# carrier_sengi.net
KiCad netlist of a schematic drawn in EAGLE
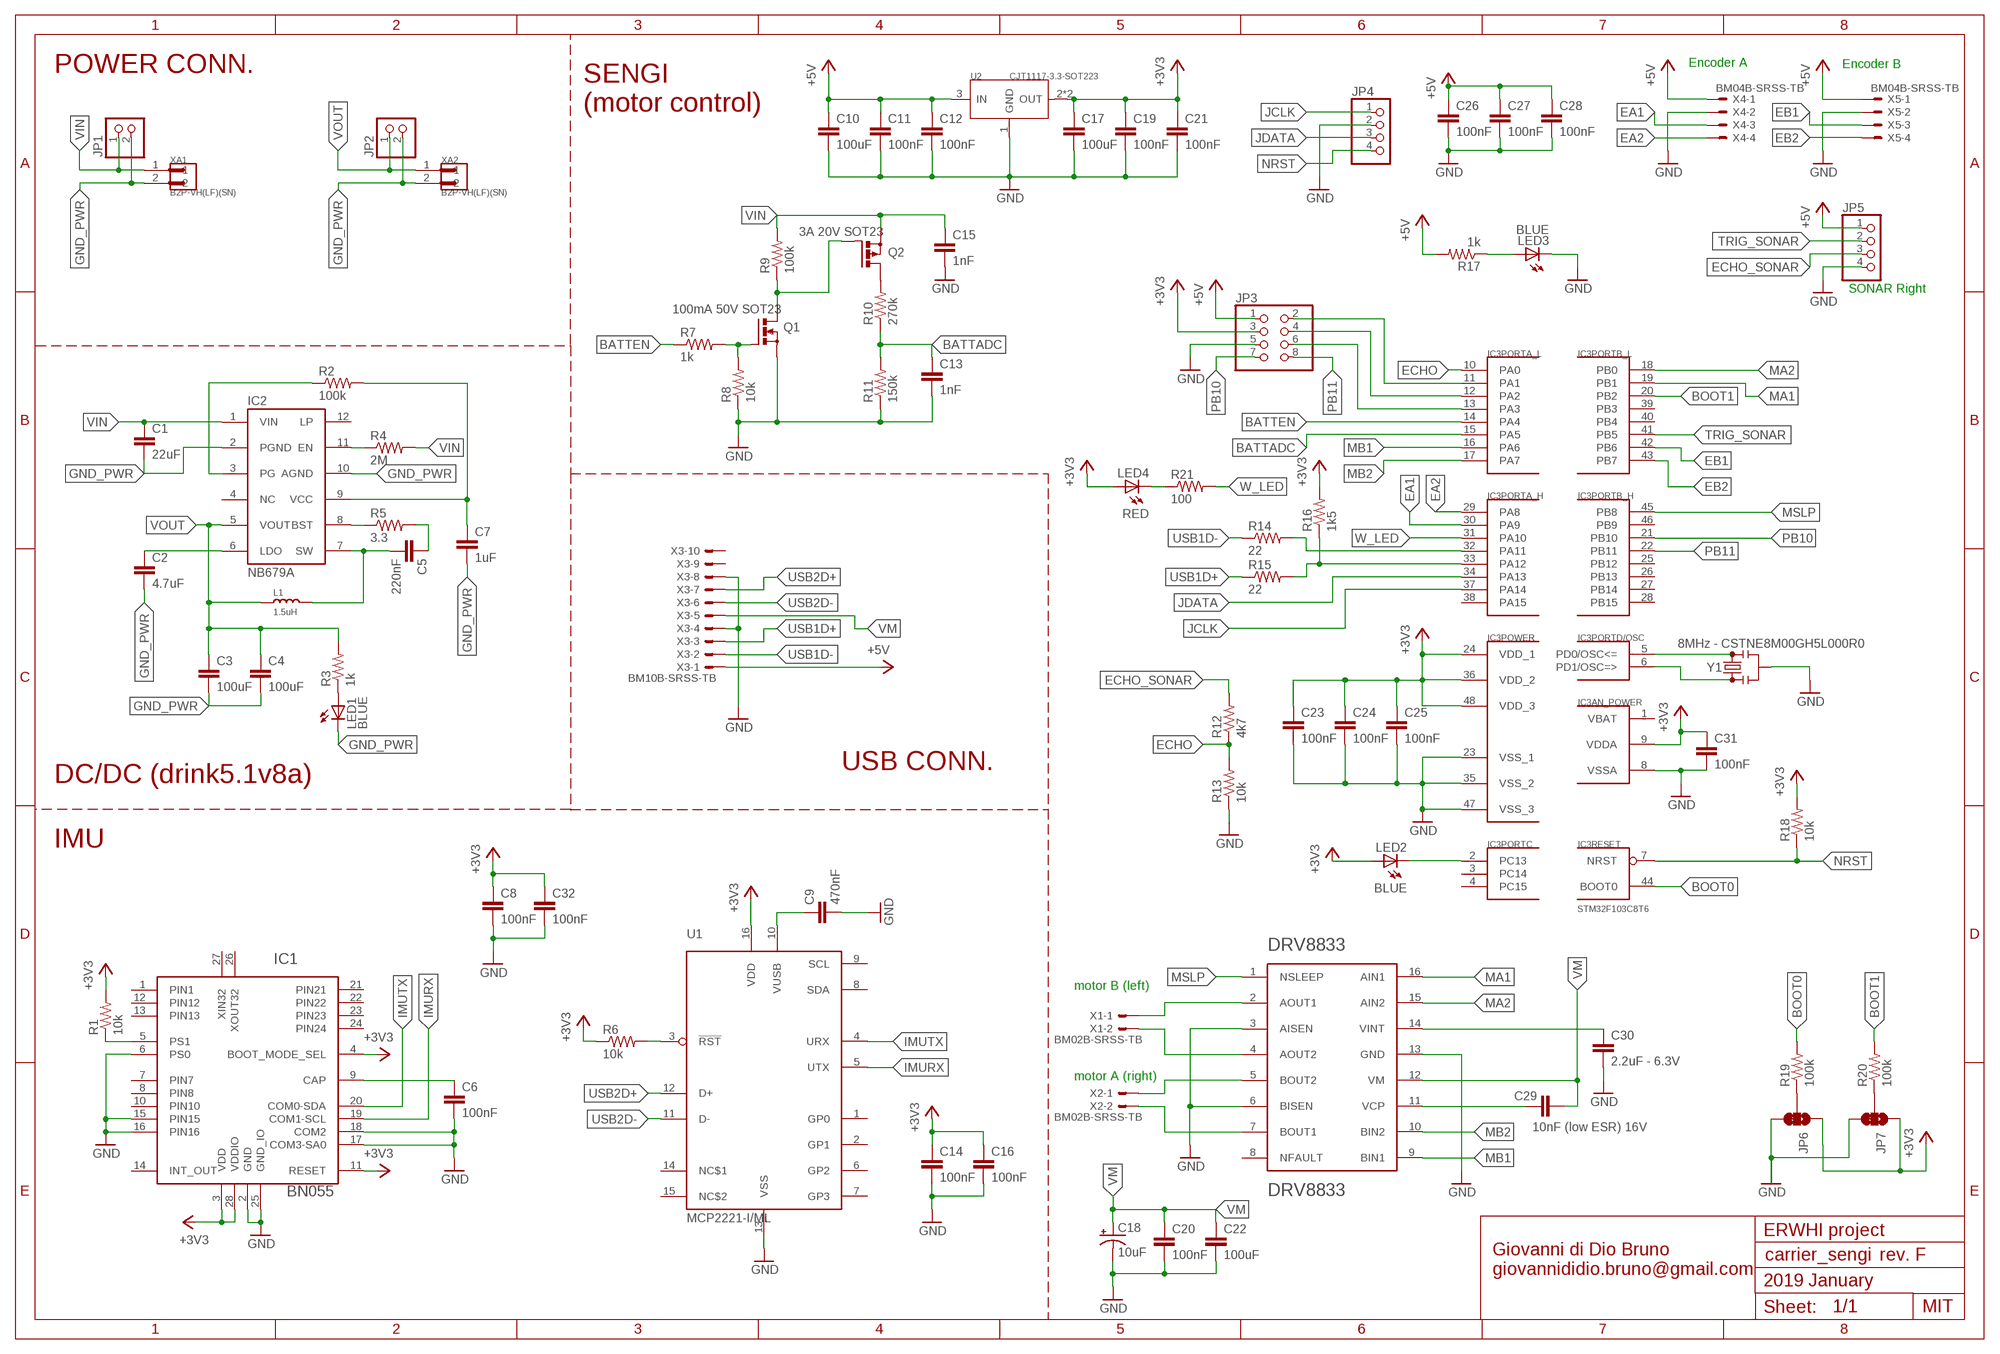
[diagram p0: schematic, sheet 1]

(export (version "E")
  (design (tool "Eeschema 10.0.6"))
  (components
    (comp (ref "C1")
      (value "22uF")
      (footprint "eagle-import:C0805")
      (libsource (lib "eagle-import") (part "C-EUC0805"))
    )
    (comp (ref "C2")
      (value "4.7uF")
      (footprint "eagle-import:C0603")
      (libsource (lib "eagle-import") (part "C-EUC0603"))
    )
    (comp (ref "C3")
      (value "100uF")
      (footprint "eagle-import:C0805")
      (libsource (lib "eagle-import") (part "C-EUC0805"))
    )
    (comp (ref "C4")
      (value "100uF")
      (footprint "eagle-import:C0805")
      (libsource (lib "eagle-import") (part "C-EUC0805"))
    )
    (comp (ref "C5")
      (value "220nF")
      (footprint "eagle-import:C0603")
      (libsource (lib "eagle-import") (part "C-EUC0603"))
    )
    (comp (ref "C6")
      (value "100nF")
      (footprint "eagle-import:C0402")
      (libsource (lib "eagle-import") (part "C-EUC0402"))
    )
    (comp (ref "C7")
      (value "1uF")
      (footprint "eagle-import:C0603")
      (libsource (lib "eagle-import") (part "C-EUC0603"))
    )
    (comp (ref "C8")
      (value "100nF")
      (footprint "eagle-import:C0402")
      (libsource (lib "eagle-import") (part "C-EUC0402"))
    )
    (comp (ref "C9")
      (value "470nF")
      (footprint "eagle-import:C0402")
      (libsource (lib "eagle-import") (part "C-EUC0402"))
    )
    (comp (ref "C10")
      (value "100uF")
      (footprint "eagle-import:C0603")
      (libsource (lib "eagle-import") (part "C-EUC0603"))
    )
    (comp (ref "C11")
      (value "100nF")
      (footprint "eagle-import:C0402")
      (libsource (lib "eagle-import") (part "C-EUC0402"))
    )
    (comp (ref "C12")
      (value "100nF")
      (footprint "eagle-import:C0402")
      (libsource (lib "eagle-import") (part "C-EUC0402"))
    )
    (comp (ref "C13")
      (value "1nF")
      (footprint "eagle-import:C0402")
      (libsource (lib "eagle-import") (part "C-EUC0402"))
    )
    (comp (ref "C14")
      (value "100nF")
      (footprint "eagle-import:C0402")
      (libsource (lib "eagle-import") (part "C-EUC0402"))
    )
    (comp (ref "C15")
      (value "1nF")
      (footprint "eagle-import:C0402")
      (libsource (lib "eagle-import") (part "C-EUC0402"))
    )
    (comp (ref "C16")
      (value "100nF")
      (footprint "eagle-import:C0402")
      (libsource (lib "eagle-import") (part "C-EUC0402"))
    )
    (comp (ref "C17")
      (value "100uF")
      (footprint "eagle-import:C0603")
      (libsource (lib "eagle-import") (part "C-EUC0603"))
    )
    (comp (ref "C18")
      (value "10uF")
      (footprint "eagle-import:EIA3216")
      (libsource (lib "eagle-import") (part "10UF-POLAR-EIA3216-16V-10%(TANT)"))
    )
    (comp (ref "C19")
      (value "100nF")
      (footprint "eagle-import:C0402")
      (libsource (lib "eagle-import") (part "C-EUC0402"))
    )
    (comp (ref "C20")
      (value "100nF")
      (footprint "eagle-import:C0402")
      (libsource (lib "eagle-import") (part "C-EUC0402"))
    )
    (comp (ref "C21")
      (value "100nF")
      (footprint "eagle-import:C0402")
      (libsource (lib "eagle-import") (part "C-EUC0402"))
    )
    (comp (ref "C22")
      (value "100uF")
      (footprint "eagle-import:C0603")
      (libsource (lib "eagle-import") (part "C-EUC0603"))
    )
    (comp (ref "C23")
      (value "100nF")
      (footprint "eagle-import:C0402")
      (libsource (lib "eagle-import") (part "C-EUC0402"))
    )
    (comp (ref "C24")
      (value "100nF")
      (footprint "eagle-import:C0402")
      (libsource (lib "eagle-import") (part "C-EUC0402"))
    )
    (comp (ref "C25")
      (value "100nF")
      (footprint "eagle-import:C0402")
      (libsource (lib "eagle-import") (part "C-EUC0402"))
    )
    (comp (ref "C26")
      (value "100nF")
      (footprint "eagle-import:C0402")
      (libsource (lib "eagle-import") (part "C-EUC0402"))
    )
    (comp (ref "C27")
      (value "100nF")
      (footprint "eagle-import:C0402")
      (libsource (lib "eagle-import") (part "C-EUC0402"))
    )
    (comp (ref "C28")
      (value "100nF")
      (footprint "eagle-import:C0402")
      (libsource (lib "eagle-import") (part "C-EUC0402"))
    )
    (comp (ref "C29")
      (value "10nF (low ESR) 16V")
      (footprint "eagle-import:C0402")
      (libsource (lib "eagle-import") (part "C-EUC0402"))
    )
    (comp (ref "C30")
      (value "2.2uF - 6.3V")
      (footprint "eagle-import:C0402")
      (libsource (lib "eagle-import") (part "C-EUC0402"))
    )
    (comp (ref "C31")
      (value "100nF")
      (footprint "eagle-import:C0402")
      (libsource (lib "eagle-import") (part "C-EUC0402"))
    )
    (comp (ref "C32")
      (value "100nF")
      (footprint "eagle-import:C0402")
      (libsource (lib "eagle-import") (part "C-EUC0402"))
    )
    (comp (ref "IC1")
      (value "BN055")
      (footprint "eagle-import:LGA-28_3.80X5.20_0.5")
      (fields (field (name "PART_NUMBER") "BNO055"))
      (libsource (lib "eagle-import") (part "1658_BNO055"))
    )
    (comp (ref "IC2")
      (value "NB679A")
      (footprint "eagle-import:QFN12_2X3")
      (libsource (lib "eagle-import") (part "NB679A"))
    )
    (comp (ref "IC3")
      (value "STM32F103C8T6")
      (footprint "eagle-import:TQFP48")
      (libsource (lib "eagle-import") (part "STM32F10XCXT6"))
    )
    (comp (ref "IC4")
      (value "DRV8833PWP")
      (footprint "eagle-import:SOP65P640X120-17N")
      (libsource (lib "eagle-import") (part "DRV8833"))
    )
    (comp (ref "JP1")
      (value "PINHD-1X2")
      (footprint "eagle-import:1X02")
      (libsource (lib "eagle-import") (part "PINHD-1X2"))
    )
    (comp (ref "JP2")
      (value "PINHD-1X2")
      (footprint "eagle-import:1X02")
      (libsource (lib "eagle-import") (part "PINHD-1X2"))
    )
    (comp (ref "JP3")
      (value "PINHD-2X4")
      (footprint "eagle-import:2X04")
      (libsource (lib "eagle-import") (part "PINHD-2X4"))
    )
    (comp (ref "JP4")
      (value "PINHD-1X4")
      (footprint "eagle-import:1X04")
      (libsource (lib "eagle-import") (part "PINHD-1X4"))
    )
    (comp (ref "JP5")
      (value "PINHD-1X4")
      (footprint "eagle-import:1X04")
      (libsource (lib "eagle-import") (part "PINHD-1X4"))
    )
    (comp (ref "JP6")
      (value "JUMPER-SMT_3_1-NC_TRACE_NO-SILK")
      (footprint "eagle-import:SMT-JUMPER_3_1-NC_TRACE_NO-SILK")
      (libsource (lib "eagle-import") (part "JUMPER-SMT_3_1-NC_TRACE_NO-SILK"))
    )
    (comp (ref "JP7")
      (value "JUMPER-SMT_3_1-NC_TRACE_NO-SILK")
      (footprint "eagle-import:SMT-JUMPER_3_1-NC_TRACE_NO-SILK")
      (libsource (lib "eagle-import") (part "JUMPER-SMT_3_1-NC_TRACE_NO-SILK"))
    )
    (comp (ref "L1")
      (value "1.5uH")
      (footprint "eagle-import:SMD-2P-L6.0XW6.0XH3.0MM")
      (fields (field (name "MPN") "CSAB0630-100M"))
      (libsource (lib "eagle-import") (part "SMD-INDUCTOR-10UH-20%(2P-6X6MM)'0630'"))
    )
    (comp (ref "LED1")
      (value "BLUE")
      (footprint "eagle-import:CHIP-LED0603")
      (libsource (lib "eagle-import") (part "LEDCHIP-LED0603"))
    )
    (comp (ref "LED2")
      (value "BLUE")
      (footprint "eagle-import:CHIP-LED0603")
      (libsource (lib "eagle-import") (part "LEDCHIP-LED0603"))
    )
    (comp (ref "LED3")
      (value "BLUE")
      (footprint "eagle-import:CHIP-LED0603")
      (libsource (lib "eagle-import") (part "LEDCHIP-LED0603"))
    )
    (comp (ref "LED4")
      (value "RED")
      (footprint "eagle-import:CHIP-LED0603")
      (libsource (lib "eagle-import") (part "LEDCHIP-LED0603"))
    )
    (comp (ref "Q1")
      (value "100mA 50V SOT23")
      (footprint "eagle-import:SOT-23")
      (libsource (lib "eagle-import") (part "IRLML6344"))
    )
    (comp (ref "Q2")
      (value "3A 20V SOT23")
      (footprint "eagle-import:SOT-23")
      (libsource (lib "eagle-import") (part "IRLML6402"))
    )
    (comp (ref "R1")
      (value "10k")
      (footprint "eagle-import:R0402")
      (libsource (lib "eagle-import") (part "R-US_R0402"))
    )
    (comp (ref "R2")
      (value "100k")
      (footprint "eagle-import:R0402")
      (libsource (lib "eagle-import") (part "R-US_R0402"))
    )
    (comp (ref "R3")
      (value "1k")
      (footprint "eagle-import:R0402")
      (libsource (lib "eagle-import") (part "R-US_R0402"))
    )
    (comp (ref "R4")
      (value "2M")
      (footprint "eagle-import:R0603")
      (libsource (lib "eagle-import") (part "R-US_R0603"))
    )
    (comp (ref "R5")
      (value "3.3")
      (footprint "eagle-import:R0603")
      (libsource (lib "eagle-import") (part "R-US_R0603"))
    )
    (comp (ref "R6")
      (value "10k")
      (footprint "eagle-import:R0402")
      (libsource (lib "eagle-import") (part "R-US_R0402"))
    )
    (comp (ref "R7")
      (value "1k")
      (footprint "eagle-import:R0402")
      (libsource (lib "eagle-import") (part "R-US_R0402"))
    )
    (comp (ref "R8")
      (value "10k")
      (footprint "eagle-import:R0402")
      (libsource (lib "eagle-import") (part "R-US_R0402"))
    )
    (comp (ref "R9")
      (value "100k")
      (footprint "eagle-import:R0402")
      (libsource (lib "eagle-import") (part "R-US_R0402"))
    )
    (comp (ref "R10")
      (value "270k")
      (footprint "eagle-import:R0402")
      (libsource (lib "eagle-import") (part "R-US_R0402"))
    )
    (comp (ref "R11")
      (value "150k")
      (footprint "eagle-import:R0402")
      (libsource (lib "eagle-import") (part "R-US_R0402"))
    )
    (comp (ref "R12")
      (value "4k7")
      (footprint "eagle-import:R0402")
      (libsource (lib "eagle-import") (part "R-US_R0402"))
    )
    (comp (ref "R13")
      (value "10k")
      (footprint "eagle-import:R0402")
      (libsource (lib "eagle-import") (part "R-US_R0402"))
    )
    (comp (ref "R14")
      (value "22")
      (footprint "eagle-import:R0402")
      (libsource (lib "eagle-import") (part "R-US_R0402"))
    )
    (comp (ref "R15")
      (value "22")
      (footprint "eagle-import:R0402")
      (libsource (lib "eagle-import") (part "R-US_R0402"))
    )
    (comp (ref "R16")
      (value "1k5")
      (footprint "eagle-import:R0402")
      (libsource (lib "eagle-import") (part "R-US_R0402"))
    )
    (comp (ref "R17")
      (value "1k")
      (footprint "eagle-import:R0402")
      (libsource (lib "eagle-import") (part "R-US_R0402"))
    )
    (comp (ref "R18")
      (value "10k")
      (footprint "eagle-import:R0402")
      (libsource (lib "eagle-import") (part "R-US_R0402"))
    )
    (comp (ref "R19")
      (value "100k")
      (footprint "eagle-import:R0402")
      (libsource (lib "eagle-import") (part "R-US_R0402"))
    )
    (comp (ref "R20")
      (value "100k")
      (footprint "eagle-import:R0402")
      (libsource (lib "eagle-import") (part "R-US_R0402"))
    )
    (comp (ref "R21")
      (value "100")
      (footprint "eagle-import:R0402")
      (libsource (lib "eagle-import") (part "R-US_R0402"))
    )
    (comp (ref "U1")
      (value "MCP2221-I/ML")
      (footprint "eagle-import:QFN16-4X4")
      (libsource (lib "eagle-import") (part "MCP2221-I/ML"))
    )
    (comp (ref "U2")
      (value "CJT1117-3.3-SOT223")
      (footprint "eagle-import:SOT-223")
      (fields (field (name "MPN") "CJT1117-3.3"))
      (libsource (lib "eagle-import") (part "PMIC-CJT1117-3.3(SOT223)"))
    )
    (comp (ref "X1")
      (value "BM02B-SRSS-TB")
      (footprint "eagle-import:BM02B-SRSS-TB")
      (libsource (lib "eagle-import") (part "?M02B-SRSS-TBB"))
    )
    (comp (ref "X2")
      (value "BM02B-SRSS-TB")
      (footprint "eagle-import:BM02B-SRSS-TB")
      (libsource (lib "eagle-import") (part "?M02B-SRSS-TBB"))
    )
    (comp (ref "X3")
      (value "BM10B-SRSS-TB")
      (footprint "eagle-import:BM10B-SRSS-TB")
      (libsource (lib "eagle-import") (part "?M10B-SRSS-TBB"))
    )
    (comp (ref "X4")
      (value "BM04B-SRSS-TB")
      (footprint "eagle-import:BM04B-SRSS-TB")
      (libsource (lib "eagle-import") (part "?M04B-SRSS-TBB"))
    )
    (comp (ref "X5")
      (value "BM04B-SRSS-TB")
      (footprint "eagle-import:BM04B-SRSS-TB")
      (libsource (lib "eagle-import") (part "?M04B-SRSS-TBB"))
    )
    (comp (ref "XA1")
      (value "B2P-VH(LF)(SN)")
      (footprint "eagle-import:JST_B2P-VH(LF)(SN)")
      (fields (field (name "MF") "JST") (field (name "MP") "B2P-VH_LF__SN_"))
      (libsource (lib "eagle-import") (part "B2P-VH(LF)(SN)"))
    )
    (comp (ref "XA2")
      (value "B2P-VH(LF)(SN)")
      (footprint "eagle-import:JST_B2P-VH(LF)(SN)")
      (fields (field (name "MF") "JST") (field (name "MP") "B2P-VH_LF__SN_"))
      (libsource (lib "eagle-import") (part "B2P-VH(LF)(SN)"))
    )
    (comp (ref "Y1")
      (value "8MHz - CSTNE8M00GH5L000R0")
      (footprint "eagle-import:RESONATOR-SMD-3.2X1.3")
      (libsource (lib "eagle-import") (part "RESONATOR-8MHZSMD_3.2X1.3"))
    )
  )
  (nets
    (net (code "1") (name "+3V3") (class "Default")
      (node (ref "C14") (pin "1") (pinfunction "1_1") (pintype "passive"))
      (node (ref "C16") (pin "1") (pinfunction "1_1") (pintype "passive"))
      (node (ref "C17") (pin "1") (pinfunction "1_1") (pintype "passive"))
      (node (ref "C19") (pin "1") (pinfunction "1_1") (pintype "passive"))
      (node (ref "C21") (pin "1") (pinfunction "1_1") (pintype "passive"))
      (node (ref "C23") (pin "1") (pinfunction "1_1") (pintype "passive"))
      (node (ref "C24") (pin "1") (pinfunction "1_1") (pintype "passive"))
      (node (ref "C25") (pin "1") (pinfunction "1_1") (pintype "passive"))
      (node (ref "C31") (pin "1") (pinfunction "1_1") (pintype "passive"))
      (node (ref "C32") (pin "1") (pinfunction "1_1") (pintype "passive"))
      (node (ref "C8") (pin "1") (pinfunction "1_1") (pintype "passive"))
      (node (ref "IC1") (pin "11") (pinfunction "RESET_11") (pintype "input"))
      (node (ref "IC1") (pin "28") (pinfunction "VDDIO_28") (pintype "power_in"))
      (node (ref "IC1") (pin "3") (pinfunction "VDD_3") (pintype "power_in"))
      (node (ref "IC1") (pin "4") (pinfunction "BOOT_MODE_SEL_4") (pintype "input"))
      (node (ref "IC3") (pin "24") (pinfunction "VDD_1_24") (pintype "power_in"))
      (node (ref "IC3") (pin "36") (pinfunction "VDD_2_36") (pintype "power_in"))
      (node (ref "IC3") (pin "48") (pinfunction "VDD_3_48") (pintype "power_in"))
      (node (ref "IC3") (pin "9") (pinfunction "VDDA_9") (pintype "power_in"))
      (node (ref "JP3") (pin "3") (pinfunction "3_3") (pintype "passive"))
      (node (ref "JP6") (pin "1") (pinfunction "1_1") (pintype "passive"))
      (node (ref "JP7") (pin "1") (pinfunction "1_1") (pintype "passive"))
      (node (ref "LED2") (pin "A") (pinfunction "A_A") (pintype "passive"))
      (node (ref "LED4") (pin "A") (pinfunction "A_A") (pintype "passive"))
      (node (ref "R1") (pin "2") (pinfunction "2_2") (pintype "passive"))
      (node (ref "R16") (pin "2") (pinfunction "2_2") (pintype "passive"))
      (node (ref "R18") (pin "2") (pinfunction "2_2") (pintype "passive"))
      (node (ref "R6") (pin "1") (pinfunction "1_1") (pintype "passive"))
      (node (ref "U1") (pin "16") (pinfunction "VDD_16") (pintype "power_in"))
      (node (ref "U2") (pin "2") (pinfunction "OUT_2") (pintype "bidirectional"))
      (node (ref "U2") (pin "TER") (pinfunction "OUT_TER") (pintype "bidirectional"))
    )
    (net (code "2") (name "+5V") (class "Default")
      (node (ref "C10") (pin "1") (pinfunction "1_1") (pintype "passive"))
      (node (ref "C11") (pin "1") (pinfunction "1_1") (pintype "passive"))
      (node (ref "C12") (pin "1") (pinfunction "1_1") (pintype "passive"))
      (node (ref "C26") (pin "1") (pinfunction "1_1") (pintype "passive"))
      (node (ref "C27") (pin "1") (pinfunction "1_1") (pintype "passive"))
      (node (ref "C28") (pin "1") (pinfunction "1_1") (pintype "passive"))
      (node (ref "JP3") (pin "1") (pinfunction "1_1") (pintype "passive"))
      (node (ref "JP5") (pin "1") (pinfunction "1_1") (pintype "passive"))
      (node (ref "R17") (pin "2") (pinfunction "2_2") (pintype "passive"))
      (node (ref "U2") (pin "3") (pinfunction "IN_3") (pintype "bidirectional"))
      (node (ref "X3") (pin "1") (pinfunction "S_1") (pintype "passive"))
      (node (ref "X4") (pin "1") (pinfunction "S_1") (pintype "passive"))
      (node (ref "X5") (pin "1") (pinfunction "S_1") (pintype "passive"))
    )
    (net (code "3") (name "/VBAT") (class "Default")
      (node (ref "IC3") (pin "1") (pinfunction "VBAT_1") (pintype "power_in"))
    )
    (net (code "4") (name "BATTADC") (class "Default")
      (node (ref "C13") (pin "1") (pinfunction "1_1") (pintype "passive"))
      (node (ref "IC3") (pin "15") (pinfunction "PA5_15") (pintype "bidirectional"))
      (node (ref "R10") (pin "1") (pinfunction "1_1") (pintype "passive"))
      (node (ref "R11") (pin "2") (pinfunction "2_2") (pintype "passive"))
    )
    (net (code "5") (name "BATTEN") (class "Default")
      (node (ref "IC3") (pin "14") (pinfunction "PA4_14") (pintype "bidirectional"))
      (node (ref "R7") (pin "1") (pinfunction "1_1") (pintype "passive"))
    )
    (net (code "6") (name "BOOT0") (class "Default")
      (node (ref "IC3") (pin "44") (pinfunction "BOOT0_44") (pintype "input"))
      (node (ref "R19") (pin "2") (pinfunction "2_2") (pintype "passive"))
    )
    (net (code "7") (name "BOOT1") (class "Default")
      (node (ref "IC3") (pin "20") (pinfunction "PB2_20") (pintype "bidirectional"))
      (node (ref "R20") (pin "2") (pinfunction "2_2") (pintype "passive"))
    )
    (net (code "8") (name "EA1") (class "Default")
      (node (ref "IC3") (pin "30") (pinfunction "PA9_30") (pintype "bidirectional"))
      (node (ref "X4") (pin "3") (pinfunction "S_3") (pintype "passive"))
    )
    (net (code "9") (name "EA2") (class "Default")
      (node (ref "IC3") (pin "29") (pinfunction "PA8_29") (pintype "bidirectional"))
      (node (ref "X4") (pin "4") (pinfunction "S_4") (pintype "passive"))
    )
    (net (code "10") (name "EB1") (class "Default")
      (node (ref "IC3") (pin "42") (pinfunction "PB6_42") (pintype "bidirectional"))
      (node (ref "X5") (pin "3") (pinfunction "S_3") (pintype "passive"))
    )
    (net (code "11") (name "EB2") (class "Default")
      (node (ref "IC3") (pin "43") (pinfunction "PB7_43") (pintype "bidirectional"))
      (node (ref "X5") (pin "4") (pinfunction "S_4") (pintype "passive"))
    )
    (net (code "12") (name "ECHO") (class "Default")
      (node (ref "IC3") (pin "10") (pinfunction "PA0_10") (pintype "bidirectional"))
      (node (ref "R12") (pin "1") (pinfunction "1_1") (pintype "passive"))
      (node (ref "R13") (pin "2") (pinfunction "2_2") (pintype "passive"))
    )
    (net (code "13") (name "ECHO_SONAR") (class "Default")
      (node (ref "JP5") (pin "3") (pinfunction "3_3") (pintype "passive"))
      (node (ref "R12") (pin "2") (pinfunction "2_2") (pintype "passive"))
    )
    (net (code "14") (name "GND") (class "Default")
      (node (ref "C10") (pin "2") (pinfunction "2_2") (pintype "passive"))
      (node (ref "C11") (pin "2") (pinfunction "2_2") (pintype "passive"))
      (node (ref "C12") (pin "2") (pinfunction "2_2") (pintype "passive"))
      (node (ref "C13") (pin "2") (pinfunction "2_2") (pintype "passive"))
      (node (ref "C14") (pin "2") (pinfunction "2_2") (pintype "passive"))
      (node (ref "C15") (pin "2") (pinfunction "2_2") (pintype "passive"))
      (node (ref "C16") (pin "2") (pinfunction "2_2") (pintype "passive"))
      (node (ref "C17") (pin "2") (pinfunction "2_2") (pintype "passive"))
      (node (ref "C18") (pin "-") (pinfunction "-_-") (pintype "passive"))
      (node (ref "C19") (pin "2") (pinfunction "2_2") (pintype "passive"))
      (node (ref "C20") (pin "2") (pinfunction "2_2") (pintype "passive"))
      (node (ref "C21") (pin "2") (pinfunction "2_2") (pintype "passive"))
      (node (ref "C22") (pin "2") (pinfunction "2_2") (pintype "passive"))
      (node (ref "C23") (pin "2") (pinfunction "2_2") (pintype "passive"))
      (node (ref "C24") (pin "2") (pinfunction "2_2") (pintype "passive"))
      (node (ref "C25") (pin "2") (pinfunction "2_2") (pintype "passive"))
      (node (ref "C26") (pin "2") (pinfunction "2_2") (pintype "passive"))
      (node (ref "C27") (pin "2") (pinfunction "2_2") (pintype "passive"))
      (node (ref "C28") (pin "2") (pinfunction "2_2") (pintype "passive"))
      (node (ref "C30") (pin "2") (pinfunction "2_2") (pintype "passive"))
      (node (ref "C31") (pin "2") (pinfunction "2_2") (pintype "passive"))
      (node (ref "C32") (pin "2") (pinfunction "2_2") (pintype "passive"))
      (node (ref "C6") (pin "2") (pinfunction "2_2") (pintype "passive"))
      (node (ref "C8") (pin "2") (pinfunction "2_2") (pintype "passive"))
      (node (ref "C9") (pin "2") (pinfunction "2_2") (pintype "passive"))
      (node (ref "IC1") (pin "15") (pinfunction "PIN15_15") (pintype "passive"))
      (node (ref "IC1") (pin "16") (pinfunction "PIN16_16") (pintype "passive"))
      (node (ref "IC1") (pin "17") (pinfunction "COM3-SA0_17") (pintype "bidirectional"))
      (node (ref "IC1") (pin "18") (pinfunction "COM2_18") (pintype "bidirectional"))
      (node (ref "IC1") (pin "2") (pinfunction "GND_2") (pintype "power_in"))
      (node (ref "IC1") (pin "25") (pinfunction "GND_IO_25") (pintype "power_in"))
      (node (ref "IC1") (pin "6") (pinfunction "PS0_6") (pintype "input"))
      (node (ref "IC3") (pin "23") (pinfunction "VSS_1_23") (pintype "power_in"))
      (node (ref "IC3") (pin "35") (pinfunction "VSS_2_35") (pintype "power_in"))
      (node (ref "IC3") (pin "47") (pinfunction "VSS_3_47") (pintype "power_in"))
      (node (ref "IC3") (pin "8") (pinfunction "VSSA_8") (pintype "power_in"))
      (node (ref "IC4") (pin "13") (pinfunction "GND_13") (pintype "bidirectional"))
      (node (ref "IC4") (pin "3") (pinfunction "AISEN_3") (pintype "bidirectional"))
      (node (ref "IC4") (pin "6") (pinfunction "BISEN_6") (pintype "bidirectional"))
      (node (ref "JP3") (pin "5") (pinfunction "5_5") (pintype "passive"))
      (node (ref "JP4") (pin "2") (pinfunction "2_2") (pintype "passive"))
      (node (ref "JP5") (pin "4") (pinfunction "4_4") (pintype "passive"))
      (node (ref "JP6") (pin "3") (pinfunction "3_3") (pintype "passive"))
      (node (ref "JP7") (pin "3") (pinfunction "3_3") (pintype "passive"))
      (node (ref "LED3") (pin "C") (pinfunction "C_C") (pintype "passive"))
      (node (ref "Q1") (pin "P2") (pinfunction "S_P2") (pintype "passive"))
      (node (ref "R11") (pin "1") (pinfunction "1_1") (pintype "passive"))
      (node (ref "R13") (pin "1") (pinfunction "1_1") (pintype "passive"))
      (node (ref "R8") (pin "1") (pinfunction "1_1") (pintype "passive"))
      (node (ref "U1") (pin "13") (pinfunction "VSS_13") (pintype "power_in"))
      (node (ref "U2") (pin "1") (pinfunction "GND_1") (pintype "bidirectional"))
      (node (ref "X3") (pin "4") (pinfunction "S_4") (pintype "passive"))
      (node (ref "X3") (pin "8") (pinfunction "S_8") (pintype "passive"))
      (node (ref "X4") (pin "2") (pinfunction "S_2") (pintype "passive"))
      (node (ref "X5") (pin "2") (pinfunction "S_2") (pintype "passive"))
      (node (ref "Y1") (pin "2") (pinfunction "2_2") (pintype "passive"))
    )
    (net (code "15") (name "GND_PWR") (class "Default")
      (node (ref "C1") (pin "2") (pinfunction "2_2") (pintype "passive"))
      (node (ref "C2") (pin "2") (pinfunction "2_2") (pintype "passive"))
      (node (ref "C3") (pin "2") (pinfunction "2_2") (pintype "passive"))
      (node (ref "C4") (pin "2") (pinfunction "2_2") (pintype "passive"))
      (node (ref "C7") (pin "2") (pinfunction "2_2") (pintype "passive"))
      (node (ref "IC2") (pin "10") (pinfunction "AGND_10") (pintype "bidirectional"))
      (node (ref "IC2") (pin "2") (pinfunction "PGND_2") (pintype "bidirectional"))
      (node (ref "JP1") (pin "2") (pinfunction "2_2") (pintype "passive"))
      (node (ref "JP2") (pin "2") (pinfunction "2_2") (pintype "passive"))
      (node (ref "LED1") (pin "C") (pinfunction "C_C") (pintype "passive"))
      (node (ref "XA1") (pin "2") (pinfunction "2_2") (pintype "passive"))
      (node (ref "XA2") (pin "2") (pinfunction "2_2") (pintype "passive"))
    )
    (net (code "16") (name "IMURX") (class "Default")
      (node (ref "IC1") (pin "19") (pinfunction "COM1-SCL_19") (pintype "bidirectional"))
      (node (ref "U1") (pin "5") (pinfunction "UTX_5") (pintype "output"))
    )
    (net (code "17") (name "IMUTX") (class "Default")
      (node (ref "IC1") (pin "20") (pinfunction "COM0-SDA_20") (pintype "bidirectional"))
      (node (ref "U1") (pin "4") (pinfunction "URX_4") (pintype "input"))
    )
    (net (code "18") (name "JCLK") (class "Default")
      (node (ref "IC3") (pin "37") (pinfunction "PA14_37") (pintype "bidirectional"))
      (node (ref "JP4") (pin "1") (pinfunction "1_1") (pintype "passive"))
    )
    (net (code "19") (name "JDATA") (class "Default")
      (node (ref "IC3") (pin "34") (pinfunction "PA13_34") (pintype "bidirectional"))
      (node (ref "JP4") (pin "3") (pinfunction "3_3") (pintype "passive"))
    )
    (net (code "20") (name "MA1") (class "Default")
      (node (ref "IC3") (pin "19") (pinfunction "PB1_19") (pintype "bidirectional"))
      (node (ref "IC4") (pin "16") (pinfunction "AIN1_16") (pintype "bidirectional"))
    )
    (net (code "21") (name "MA2") (class "Default")
      (node (ref "IC3") (pin "18") (pinfunction "PB0_18") (pintype "bidirectional"))
      (node (ref "IC4") (pin "15") (pinfunction "AIN2_15") (pintype "bidirectional"))
    )
    (net (code "22") (name "MB1") (class "Default")
      (node (ref "IC3") (pin "16") (pinfunction "PA6_16") (pintype "bidirectional"))
      (node (ref "IC4") (pin "9") (pinfunction "BIN1_9") (pintype "bidirectional"))
    )
    (net (code "23") (name "MB2") (class "Default")
      (node (ref "IC3") (pin "17") (pinfunction "PA7_17") (pintype "bidirectional"))
      (node (ref "IC4") (pin "10") (pinfunction "BIN2_10") (pintype "bidirectional"))
    )
    (net (code "24") (name "MSLP") (class "Default")
      (node (ref "IC3") (pin "45") (pinfunction "PB8_45") (pintype "bidirectional"))
      (node (ref "IC4") (pin "1") (pinfunction "NSLEEP_1") (pintype "bidirectional"))
    )
    (net (code "25") (name "NRST") (class "Default")
      (node (ref "IC3") (pin "7") (pinfunction "NRST_7") (pintype "input"))
      (node (ref "JP4") (pin "4") (pinfunction "4_4") (pintype "passive"))
      (node (ref "R18") (pin "1") (pinfunction "1_1") (pintype "passive"))
    )
    (net (code "26") (name "Net-(C5-Pad1)") (class "Default")
      (node (ref "C5") (pin "1") (pinfunction "1_1") (pintype "passive"))
      (node (ref "R5") (pin "2") (pinfunction "2_2") (pintype "passive"))
    )
    (net (code "27") (name "Net-(IC1-CAP)") (class "Default")
      (node (ref "C6") (pin "1") (pinfunction "1_1") (pintype "passive"))
      (node (ref "IC1") (pin "9") (pinfunction "CAP_9") (pintype "tri_state"))
    )
    (net (code "28") (name "Net-(IC1-PS1)") (class "Default")
      (node (ref "IC1") (pin "5") (pinfunction "PS1_5") (pintype "input"))
      (node (ref "R1") (pin "1") (pinfunction "1_1") (pintype "passive"))
    )
    (net (code "29") (name "Net-(IC2-BST)") (class "Default")
      (node (ref "IC2") (pin "8") (pinfunction "BST_8") (pintype "bidirectional"))
      (node (ref "R5") (pin "1") (pinfunction "1_1") (pintype "passive"))
    )
    (net (code "30") (name "Net-(IC2-EN)") (class "Default")
      (node (ref "IC2") (pin "11") (pinfunction "EN_11") (pintype "bidirectional"))
      (node (ref "R4") (pin "1") (pinfunction "1_1") (pintype "passive"))
    )
    (net (code "31") (name "Net-(IC2-LDO)") (class "Default")
      (node (ref "C2") (pin "1") (pinfunction "1_1") (pintype "passive"))
      (node (ref "IC2") (pin "6") (pinfunction "LDO_6") (pintype "bidirectional"))
    )
    (net (code "32") (name "Net-(IC2-PG)") (class "Default")
      (node (ref "IC2") (pin "3") (pinfunction "PG_3") (pintype "bidirectional"))
      (node (ref "R2") (pin "1") (pinfunction "1_1") (pintype "passive"))
    )
    (net (code "33") (name "Net-(IC2-SW)") (class "Default")
      (node (ref "C5") (pin "2") (pinfunction "2_2") (pintype "passive"))
      (node (ref "IC2") (pin "7") (pinfunction "SW_7") (pintype "bidirectional"))
      (node (ref "L1") (pin "2") (pinfunction "2_2") (pintype "passive"))
    )
    (net (code "34") (name "Net-(IC2-VCC)") (class "Default")
      (node (ref "C7") (pin "1") (pinfunction "1_1") (pintype "passive"))
      (node (ref "IC2") (pin "9") (pinfunction "VCC_9") (pintype "bidirectional"))
      (node (ref "R2") (pin "2") (pinfunction "2_2") (pintype "passive"))
    )
    (net (code "35") (name "Net-(IC3B-PA11)") (class "Default")
      (node (ref "IC3") (pin "32") (pinfunction "PA11_32") (pintype "bidirectional"))
      (node (ref "R14") (pin "2") (pinfunction "2_2") (pintype "passive"))
    )
    (net (code "36") (name "Net-(IC3B-PA12)") (class "Default")
      (node (ref "IC3") (pin "33") (pinfunction "PA12_33") (pintype "bidirectional"))
      (node (ref "R15") (pin "2") (pinfunction "2_2") (pintype "passive"))
      (node (ref "R16") (pin "1") (pinfunction "1_1") (pintype "passive"))
    )
    (net (code "37") (name "Net-(IC3C-PA1)") (class "Default")
      (node (ref "IC3") (pin "11") (pinfunction "PA1_11") (pintype "bidirectional"))
      (node (ref "JP3") (pin "2") (pinfunction "2_2") (pintype "passive"))
    )
    (net (code "38") (name "Net-(IC3C-PA2)") (class "Default")
      (node (ref "IC3") (pin "12") (pinfunction "PA2_12") (pintype "bidirectional"))
      (node (ref "JP3") (pin "4") (pinfunction "4_4") (pintype "passive"))
    )
    (net (code "39") (name "Net-(IC3C-PA3)") (class "Default")
      (node (ref "IC3") (pin "13") (pinfunction "PA3_13") (pintype "bidirectional"))
      (node (ref "JP3") (pin "6") (pinfunction "6_6") (pintype "passive"))
    )
    (net (code "40") (name "Net-(IC3F-PC13)") (class "Default")
      (node (ref "IC3") (pin "2") (pinfunction "PC13_2") (pintype "bidirectional"))
      (node (ref "LED2") (pin "C") (pinfunction "C_C") (pintype "passive"))
    )
    (net (code "41") (name "Net-(IC3G-PD0{slash}OSC<=)") (class "Default")
      (node (ref "IC3") (pin "5") (pinfunction "PD0/OSC<=_5") (pintype "bidirectional"))
      (node (ref "Y1") (pin "3") (pinfunction "3_3") (pintype "passive"))
    )
    (net (code "42") (name "Net-(IC3G-PD1{slash}OSC=>)") (class "Default")
      (node (ref "IC3") (pin "6") (pinfunction "PD1/OSC=>_6") (pintype "bidirectional"))
      (node (ref "Y1") (pin "1") (pinfunction "1_1") (pintype "passive"))
    )
    (net (code "43") (name "Net-(IC4-AOUT1)") (class "Default")
      (node (ref "IC4") (pin "2") (pinfunction "AOUT1_2") (pintype "bidirectional"))
      (node (ref "X1") (pin "1") (pinfunction "S_1") (pintype "passive"))
    )
    (net (code "44") (name "Net-(IC4-AOUT2)") (class "Default")
      (node (ref "IC4") (pin "4") (pinfunction "AOUT2_4") (pintype "bidirectional"))
      (node (ref "X1") (pin "2") (pinfunction "S_2") (pintype "passive"))
    )
    (net (code "45") (name "Net-(IC4-BOUT1)") (class "Default")
      (node (ref "IC4") (pin "7") (pinfunction "BOUT1_7") (pintype "bidirectional"))
      (node (ref "X2") (pin "2") (pinfunction "S_2") (pintype "passive"))
    )
    (net (code "46") (name "Net-(IC4-BOUT2)") (class "Default")
      (node (ref "IC4") (pin "5") (pinfunction "BOUT2_5") (pintype "bidirectional"))
      (node (ref "X2") (pin "1") (pinfunction "S_1") (pintype "passive"))
    )
    (net (code "47") (name "Net-(IC4-VCP)") (class "Default")
      (node (ref "C29") (pin "2") (pinfunction "2_2") (pintype "passive"))
      (node (ref "IC4") (pin "11") (pinfunction "VCP_11") (pintype "bidirectional"))
    )
    (net (code "48") (name "Net-(IC4-VINT)") (class "Default")
      (node (ref "C30") (pin "1") (pinfunction "1_1") (pintype "passive"))
      (node (ref "IC4") (pin "14") (pinfunction "VINT_14") (pintype "bidirectional"))
    )
    (net (code "49") (name "Net-(JP6-Pad2)") (class "Default")
      (node (ref "JP6") (pin "2") (pinfunction "2_2") (pintype "passive"))
      (node (ref "R19") (pin "1") (pinfunction "1_1") (pintype "passive"))
    )
    (net (code "50") (name "Net-(JP7-Pad2)") (class "Default")
      (node (ref "JP7") (pin "2") (pinfunction "2_2") (pintype "passive"))
      (node (ref "R20") (pin "1") (pinfunction "1_1") (pintype "passive"))
    )
    (net (code "51") (name "Net-(LED1-PadA)") (class "Default")
      (node (ref "LED1") (pin "A") (pinfunction "A_A") (pintype "passive"))
      (node (ref "R3") (pin "1") (pinfunction "1_1") (pintype "passive"))
    )
    (net (code "52") (name "Net-(LED3-PadA)") (class "Default")
      (node (ref "LED3") (pin "A") (pinfunction "A_A") (pintype "passive"))
      (node (ref "R17") (pin "1") (pinfunction "1_1") (pintype "passive"))
    )
    (net (code "53") (name "Net-(LED4-PadC)") (class "Default")
      (node (ref "LED4") (pin "C") (pinfunction "C_C") (pintype "passive"))
      (node (ref "R21") (pin "1") (pinfunction "1_1") (pintype "passive"))
    )
    (net (code "54") (name "Net-(Q1-D)") (class "Default")
      (node (ref "Q1") (pin "P3") (pinfunction "D_P3") (pintype "passive"))
      (node (ref "Q2") (pin "P1") (pinfunction "G_P1") (pintype "passive"))
      (node (ref "R9") (pin "1") (pinfunction "1_1") (pintype "passive"))
    )
    (net (code "55") (name "Net-(Q1-G)") (class "Default")
      (node (ref "Q1") (pin "P1") (pinfunction "G_P1") (pintype "passive"))
      (node (ref "R7") (pin "2") (pinfunction "2_2") (pintype "passive"))
      (node (ref "R8") (pin "2") (pinfunction "2_2") (pintype "passive"))
    )
    (net (code "56") (name "Net-(Q2-D)") (class "Default")
      (node (ref "Q2") (pin "P3") (pinfunction "D_P3") (pintype "passive"))
      (node (ref "R10") (pin "2") (pinfunction "2_2") (pintype "passive"))
    )
    (net (code "57") (name "Net-(U1-VUSB)") (class "Default")
      (node (ref "C9") (pin "1") (pinfunction "1_1") (pintype "passive"))
      (node (ref "U1") (pin "10") (pinfunction "VUSB_10") (pintype "power_in"))
    )
    (net (code "58") (name "Net-(U1-~{RST})") (class "Default")
      (node (ref "R6") (pin "2") (pinfunction "2_2") (pintype "passive"))
      (node (ref "U1") (pin "3") (pinfunction "~{RST}_3") (pintype "input"))
    )
    (net (code "59") (name "PB10") (class "Default")
      (node (ref "IC3") (pin "21") (pinfunction "PB10_21") (pintype "bidirectional"))
      (node (ref "JP3") (pin "7") (pinfunction "7_7") (pintype "passive"))
    )
    (net (code "60") (name "PB11") (class "Default")
      (node (ref "IC3") (pin "22") (pinfunction "PB11_22") (pintype "bidirectional"))
      (node (ref "JP3") (pin "8") (pinfunction "8_8") (pintype "passive"))
    )
    (net (code "61") (name "TRIG_SONAR") (class "Default")
      (node (ref "IC3") (pin "41") (pinfunction "PB5_41") (pintype "bidirectional"))
      (node (ref "JP5") (pin "2") (pinfunction "2_2") (pintype "passive"))
    )
    (net (code "62") (name "USB1D+") (class "Default")
      (node (ref "R15") (pin "1") (pinfunction "1_1") (pintype "passive"))
      (node (ref "X3") (pin "3") (pinfunction "S_3") (pintype "passive"))
    )
    (net (code "63") (name "USB1D-") (class "Default")
      (node (ref "R14") (pin "1") (pinfunction "1_1") (pintype "passive"))
      (node (ref "X3") (pin "2") (pinfunction "S_2") (pintype "passive"))
    )
    (net (code "64") (name "USB2D+") (class "Default")
      (node (ref "U1") (pin "12") (pinfunction "D+_12") (pintype "bidirectional"))
      (node (ref "X3") (pin "7") (pinfunction "S_7") (pintype "passive"))
    )
    (net (code "65") (name "USB2D-") (class "Default")
      (node (ref "U1") (pin "11") (pinfunction "D-_11") (pintype "bidirectional"))
      (node (ref "X3") (pin "6") (pinfunction "S_6") (pintype "passive"))
    )
    (net (code "66") (name "VIN") (class "Default")
      (node (ref "C1") (pin "1") (pinfunction "1_1") (pintype "passive"))
      (node (ref "C15") (pin "1") (pinfunction "1_1") (pintype "passive"))
      (node (ref "IC2") (pin "1") (pinfunction "VIN_1") (pintype "bidirectional"))
      (node (ref "JP1") (pin "1") (pinfunction "1_1") (pintype "passive"))
      (node (ref "Q2") (pin "P2") (pinfunction "S_P2") (pintype "passive"))
      (node (ref "R4") (pin "2") (pinfunction "2_2") (pintype "passive"))
      (node (ref "R9") (pin "2") (pinfunction "2_2") (pintype "passive"))
      (node (ref "XA1") (pin "1") (pinfunction "1_1") (pintype "passive"))
    )
    (net (code "67") (name "VM") (class "Default")
      (node (ref "C18") (pin "+") (pinfunction "+_+") (pintype "passive"))
      (node (ref "C20") (pin "1") (pinfunction "1_1") (pintype "passive"))
      (node (ref "C22") (pin "1") (pinfunction "1_1") (pintype "passive"))
      (node (ref "C29") (pin "1") (pinfunction "1_1") (pintype "passive"))
      (node (ref "IC4") (pin "12") (pinfunction "VM_12") (pintype "bidirectional"))
      (node (ref "X3") (pin "5") (pinfunction "S_5") (pintype "passive"))
    )
    (net (code "68") (name "VOUT") (class "Default")
      (node (ref "C3") (pin "1") (pinfunction "1_1") (pintype "passive"))
      (node (ref "C4") (pin "1") (pinfunction "1_1") (pintype "passive"))
      (node (ref "IC2") (pin "5") (pinfunction "VOUT_5") (pintype "bidirectional"))
      (node (ref "JP2") (pin "1") (pinfunction "1_1") (pintype "passive"))
      (node (ref "L1") (pin "1") (pinfunction "1_1") (pintype "passive"))
      (node (ref "R3") (pin "2") (pinfunction "2_2") (pintype "passive"))
      (node (ref "XA2") (pin "1") (pinfunction "1_1") (pintype "passive"))
    )
    (net (code "69") (name "W_LED") (class "Default")
      (node (ref "IC3") (pin "31") (pinfunction "PA10_31") (pintype "bidirectional"))
      (node (ref "R21") (pin "2") (pinfunction "2_2") (pintype "passive"))
    )
    (net (code "70") (name "unconnected-(IC1-INT_OUT-Pad14)") (class "Default")
      (node (ref "IC1") (pin "14") (pinfunction "INT_OUT_14") (pintype "output"))
    )
    (net (code "71") (name "unconnected-(IC1-PIN1-Pad1)") (class "Default")
      (node (ref "IC1") (pin "1") (pinfunction "PIN1_1") (pintype "no_connect"))
    )
    (net (code "72") (name "unconnected-(IC1-PIN7-Pad7)") (class "Default")
      (node (ref "IC1") (pin "7") (pinfunction "PIN7_7") (pintype "tri_state"))
    )
    (net (code "73") (name "unconnected-(IC1-PIN8-Pad8)") (class "Default")
      (node (ref "IC1") (pin "8") (pinfunction "PIN8_8") (pintype "tri_state"))
    )
    (net (code "74") (name "unconnected-(IC1-PIN10-Pad10)") (class "Default")
      (node (ref "IC1") (pin "10") (pinfunction "PIN10_10") (pintype "passive"))
    )
    (net (code "75") (name "unconnected-(IC1-PIN12-Pad12)") (class "Default")
      (node (ref "IC1") (pin "12") (pinfunction "PIN12_12") (pintype "passive"))
    )
    (net (code "76") (name "unconnected-(IC1-PIN13-Pad13)") (class "Default")
      (node (ref "IC1") (pin "13") (pinfunction "PIN13_13") (pintype "passive"))
    )
    (net (code "77") (name "unconnected-(IC1-PIN21-Pad21)") (class "Default")
      (node (ref "IC1") (pin "21") (pinfunction "PIN21_21") (pintype "passive"))
    )
    (net (code "78") (name "unconnected-(IC1-PIN22-Pad22)") (class "Default")
      (node (ref "IC1") (pin "22") (pinfunction "PIN22_22") (pintype "passive"))
    )
    (net (code "79") (name "unconnected-(IC1-PIN23-Pad23)") (class "Default")
      (node (ref "IC1") (pin "23") (pinfunction "PIN23_23") (pintype "passive"))
    )
    (net (code "80") (name "unconnected-(IC1-PIN24-Pad24)") (class "Default")
      (node (ref "IC1") (pin "24") (pinfunction "PIN24_24") (pintype "passive"))
    )
    (net (code "81") (name "unconnected-(IC1-XIN32-Pad27)") (class "Default")
      (node (ref "IC1") (pin "27") (pinfunction "XIN32_27") (pintype "bidirectional"))
    )
    (net (code "82") (name "unconnected-(IC1-XOUT32-Pad26)") (class "Default")
      (node (ref "IC1") (pin "26") (pinfunction "XOUT32_26") (pintype "output"))
    )
    (net (code "83") (name "unconnected-(IC2-LP-Pad12)") (class "Default")
      (node (ref "IC2") (pin "12") (pinfunction "LP_12") (pintype "bidirectional"))
    )
    (net (code "84") (name "unconnected-(IC2-NC-Pad4)") (class "Default")
      (node (ref "IC2") (pin "4") (pinfunction "NC_4") (pintype "bidirectional"))
    )
    (net (code "85") (name "unconnected-(IC3B-PA15-Pad38)") (class "Default")
      (node (ref "IC3") (pin "38") (pinfunction "PA15_38") (pintype "bidirectional"))
    )
    (net (code "86") (name "unconnected-(IC3D-PB9-Pad46)") (class "Default")
      (node (ref "IC3") (pin "46") (pinfunction "PB9_46") (pintype "bidirectional"))
    )
    (net (code "87") (name "unconnected-(IC3D-PB12-Pad25)") (class "Default")
      (node (ref "IC3") (pin "25") (pinfunction "PB12_25") (pintype "bidirectional"))
    )
    (net (code "88") (name "unconnected-(IC3D-PB13-Pad26)") (class "Default")
      (node (ref "IC3") (pin "26") (pinfunction "PB13_26") (pintype "bidirectional"))
    )
    (net (code "89") (name "unconnected-(IC3D-PB14-Pad27)") (class "Default")
      (node (ref "IC3") (pin "27") (pinfunction "PB14_27") (pintype "bidirectional"))
    )
    (net (code "90") (name "unconnected-(IC3D-PB15-Pad28)") (class "Default")
      (node (ref "IC3") (pin "28") (pinfunction "PB15_28") (pintype "bidirectional"))
    )
    (net (code "91") (name "unconnected-(IC3E-PB3-Pad39)") (class "Default")
      (node (ref "IC3") (pin "39") (pinfunction "PB3_39") (pintype "bidirectional"))
    )
    (net (code "92") (name "unconnected-(IC3E-PB4-Pad40)") (class "Default")
      (node (ref "IC3") (pin "40") (pinfunction "PB4_40") (pintype "bidirectional"))
    )
    (net (code "93") (name "unconnected-(IC3F-PC14-Pad3)") (class "Default")
      (node (ref "IC3") (pin "3") (pinfunction "PC14_3") (pintype "bidirectional"))
    )
    (net (code "94") (name "unconnected-(IC3F-PC15-Pad4)") (class "Default")
      (node (ref "IC3") (pin "4") (pinfunction "PC15_4") (pintype "bidirectional"))
    )
    (net (code "95") (name "unconnected-(IC4-NFAULT-Pad8)") (class "Default")
      (node (ref "IC4") (pin "8") (pinfunction "NFAULT_8") (pintype "bidirectional"))
    )
    (net (code "96") (name "unconnected-(U1-GP0-Pad1)") (class "Default")
      (node (ref "U1") (pin "1") (pinfunction "GP0_1") (pintype "bidirectional"))
    )
    (net (code "97") (name "unconnected-(U1-GP1-Pad2)") (class "Default")
      (node (ref "U1") (pin "2") (pinfunction "GP1_2") (pintype "bidirectional"))
    )
    (net (code "98") (name "unconnected-(U1-GP2-Pad6)") (class "Default")
      (node (ref "U1") (pin "6") (pinfunction "GP2_6") (pintype "bidirectional"))
    )
    (net (code "99") (name "unconnected-(U1-GP3-Pad7)") (class "Default")
      (node (ref "U1") (pin "7") (pinfunction "GP3_7") (pintype "bidirectional"))
    )
    (net (code "100") (name "unconnected-(U1-NC$1-Pad14)") (class "Default")
      (node (ref "U1") (pin "14") (pinfunction "NC$1_14") (pintype "no_connect"))
    )
    (net (code "101") (name "unconnected-(U1-NC$2-Pad15)") (class "Default")
      (node (ref "U1") (pin "15") (pinfunction "NC$2_15") (pintype "no_connect"))
    )
    (net (code "102") (name "unconnected-(U1-SCL-Pad9)") (class "Default")
      (node (ref "U1") (pin "9") (pinfunction "SCL_9") (pintype "output"))
    )
    (net (code "103") (name "unconnected-(U1-SDA-Pad8)") (class "Default")
      (node (ref "U1") (pin "8") (pinfunction "SDA_8") (pintype "bidirectional"))
    )
    (net (code "104") (name "unconnected-(X3B-S-Pad10)") (class "Default")
      (node (ref "X3") (pin "10") (pinfunction "S_10") (pintype "passive"))
    )
    (net (code "105") (name "unconnected-(X3J-S-Pad9)") (class "Default")
      (node (ref "X3") (pin "9") (pinfunction "S_9") (pintype "passive"))
    )
  )
)
